# main.net
KiCad netlist of a schematic drawn in EAGLE
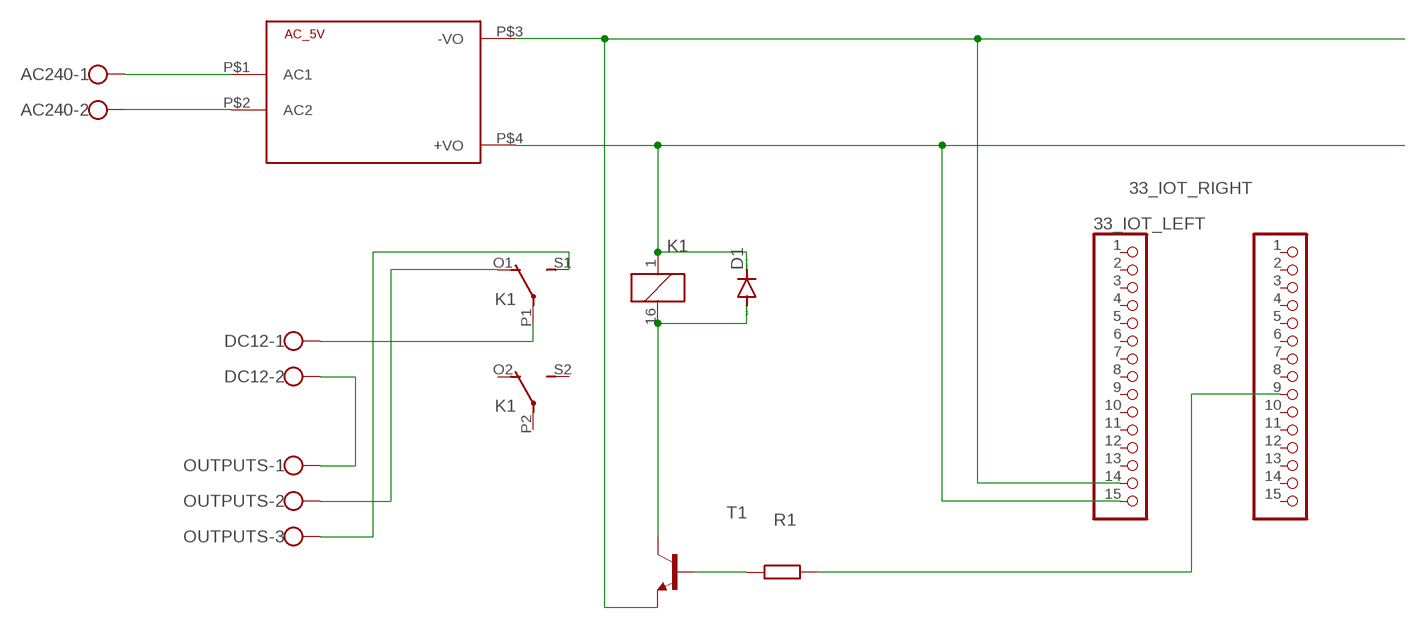
[diagram p0: schematic, sheet 1]

(export (version "E")
  (design (tool "Eeschema 10.0.6"))
  (components
    (comp (ref "33_IOT_LEFT")
      (value "PINHD-1X15")
      (footprint "eagle-import:1X15")
      (libsource (lib "eagle-import") (part "PINHD-1X15"))
    )
    (comp (ref "33_IOT_RIGHT")
      (value "PINHD-1X15")
      (footprint "eagle-import:1X15")
      (libsource (lib "eagle-import") (part "PINHD-1X15"))
    )
    (comp (ref "AC240")
      (value "W237-102")
      (footprint "eagle-import:W237-102")
      (fields (field (name "MPN") "237-102"))
      (libsource (lib "eagle-import") (part "W237-102"))
    )
    (comp (ref "AC_5V")
      (value "HLK-PM013W")
      (footprint "eagle-import:HLK-PM01")
      (libsource (lib "eagle-import") (part "HLK-PM013W"))
    )
    (comp (ref "D1")
      (value "1N5060GP")
      (footprint "eagle-import:DO15-12")
      (libsource (lib "eagle-import") (part "1N5060GP"))
    )
    (comp (ref "DC12")
      (value "W237-102")
      (footprint "eagle-import:W237-102")
      (fields (field (name "MPN") "237-102"))
      (libsource (lib "eagle-import") (part "W237-102"))
    )
    (comp (ref "K1")
      (value "351")
      (footprint "eagle-import:351")
      (libsource (lib "eagle-import") (part "351"))
    )
    (comp (ref "OUTPUTS")
      (value "W237-103")
      (footprint "eagle-import:W237-103")
      (fields (field (name "MPN") "237-103"))
      (libsource (lib "eagle-import") (part "W237-103"))
    )
    (comp (ref "R1")
      (value "R-EU_0207/10")
      (footprint "eagle-import:0207_10")
      (libsource (lib "eagle-import") (part "R-EU_0207/10"))
    )
    (comp (ref "T1")
      (value "2N2222")
      (footprint "eagle-import:TO18")
      (libsource (lib "eagle-import") (part "2N2222"))
    )
  )
  (nets
    (net (code "1") (name "Net-(33_IOT_RIGHT-Pad9)") (class "Default")
      (node (ref "33_IOT_RIGHT") (pin "9") (pinfunction "9_9") (pintype "passive"))
      (node (ref "R1") (pin "2") (pinfunction "2_2") (pintype "passive"))
    )
    (net (code "2") (name "Net-(AC240A-KL)") (class "Default")
      (node (ref "AC240") (pin "1") (pinfunction "KL_1") (pintype "passive"))
      (node (ref "AC_5V") (pin "P$1") (pinfunction "AC1_P$1") (pintype "bidirectional"))
    )
    (net (code "3") (name "Net-(AC240B-KL)") (class "Default")
      (node (ref "AC240") (pin "2") (pinfunction "KL_2") (pintype "passive"))
      (node (ref "AC_5V") (pin "P$2") (pinfunction "AC2_P$2") (pintype "bidirectional"))
    )
    (net (code "4") (name "Net-(AC_5V-+VO)") (class "Default")
      (node (ref "33_IOT_LEFT") (pin "15") (pinfunction "15_15") (pintype "passive"))
      (node (ref "AC_5V") (pin "P$4") (pinfunction "+VO_P$4") (pintype "bidirectional"))
      (node (ref "D1") (pin "C") (pinfunction "C_C") (pintype "passive"))
      (node (ref "K1") (pin "1") (pinfunction "1_1") (pintype "passive"))
    )
    (net (code "5") (name "Net-(AC_5V--VO)") (class "Default")
      (node (ref "33_IOT_LEFT") (pin "14") (pinfunction "14_14") (pintype "passive"))
      (node (ref "AC_5V") (pin "P$3") (pinfunction "-VO_P$3") (pintype "bidirectional"))
      (node (ref "T1") (pin "1") (pinfunction "E_1") (pintype "passive"))
    )
    (net (code "6") (name "Net-(DC12A-KL)") (class "Default")
      (node (ref "DC12") (pin "1") (pinfunction "KL_1") (pintype "passive"))
      (node (ref "K1") (pin "P1") (pinfunction "P_P1") (pintype "passive"))
    )
    (net (code "7") (name "Net-(DC12B-KL)") (class "Default")
      (node (ref "DC12") (pin "2") (pinfunction "KL_2") (pintype "passive"))
      (node (ref "OUTPUTS") (pin "1") (pinfunction "KL_1") (pintype "passive"))
    )
    (net (code "8") (name "Net-(K1A-2)") (class "Default")
      (node (ref "D1") (pin "A") (pinfunction "A_A") (pintype "passive"))
      (node (ref "K1") (pin "16") (pinfunction "2_16") (pintype "passive"))
      (node (ref "T1") (pin "3") (pinfunction "C_3") (pintype "passive"))
    )
    (net (code "9") (name "Net-(K1B-O)") (class "Default")
      (node (ref "K1") (pin "O1") (pinfunction "O_O1") (pintype "passive"))
      (node (ref "OUTPUTS") (pin "2") (pinfunction "KL_2") (pintype "passive"))
    )
    (net (code "10") (name "Net-(K1B-S)") (class "Default")
      (node (ref "K1") (pin "S1") (pinfunction "S_S1") (pintype "passive"))
      (node (ref "OUTPUTS") (pin "3") (pinfunction "KL_3") (pintype "passive"))
    )
    (net (code "11") (name "Net-(T1-B)") (class "Default")
      (node (ref "R1") (pin "1") (pinfunction "1_1") (pintype "passive"))
      (node (ref "T1") (pin "2") (pinfunction "B_2") (pintype "passive"))
    )
    (net (code "12") (name "unconnected-(33_IOT_LEFT-Pad1)") (class "Default")
      (node (ref "33_IOT_LEFT") (pin "1") (pinfunction "1_1") (pintype "passive"))
    )
    (net (code "13") (name "unconnected-(33_IOT_LEFT-Pad2)") (class "Default")
      (node (ref "33_IOT_LEFT") (pin "2") (pinfunction "2_2") (pintype "passive"))
    )
    (net (code "14") (name "unconnected-(33_IOT_LEFT-Pad3)") (class "Default")
      (node (ref "33_IOT_LEFT") (pin "3") (pinfunction "3_3") (pintype "passive"))
    )
    (net (code "15") (name "unconnected-(33_IOT_LEFT-Pad4)") (class "Default")
      (node (ref "33_IOT_LEFT") (pin "4") (pinfunction "4_4") (pintype "passive"))
    )
    (net (code "16") (name "unconnected-(33_IOT_LEFT-Pad5)") (class "Default")
      (node (ref "33_IOT_LEFT") (pin "5") (pinfunction "5_5") (pintype "passive"))
    )
    (net (code "17") (name "unconnected-(33_IOT_LEFT-Pad6)") (class "Default")
      (node (ref "33_IOT_LEFT") (pin "6") (pinfunction "6_6") (pintype "passive"))
    )
    (net (code "18") (name "unconnected-(33_IOT_LEFT-Pad7)") (class "Default")
      (node (ref "33_IOT_LEFT") (pin "7") (pinfunction "7_7") (pintype "passive"))
    )
    (net (code "19") (name "unconnected-(33_IOT_LEFT-Pad8)") (class "Default")
      (node (ref "33_IOT_LEFT") (pin "8") (pinfunction "8_8") (pintype "passive"))
    )
    (net (code "20") (name "unconnected-(33_IOT_LEFT-Pad9)") (class "Default")
      (node (ref "33_IOT_LEFT") (pin "9") (pinfunction "9_9") (pintype "passive"))
    )
    (net (code "21") (name "unconnected-(33_IOT_LEFT-Pad10)") (class "Default")
      (node (ref "33_IOT_LEFT") (pin "10") (pinfunction "10_10") (pintype "passive"))
    )
    (net (code "22") (name "unconnected-(33_IOT_LEFT-Pad11)") (class "Default")
      (node (ref "33_IOT_LEFT") (pin "11") (pinfunction "11_11") (pintype "passive"))
    )
    (net (code "23") (name "unconnected-(33_IOT_LEFT-Pad12)") (class "Default")
      (node (ref "33_IOT_LEFT") (pin "12") (pinfunction "12_12") (pintype "passive"))
    )
    (net (code "24") (name "unconnected-(33_IOT_LEFT-Pad13)") (class "Default")
      (node (ref "33_IOT_LEFT") (pin "13") (pinfunction "13_13") (pintype "passive"))
    )
    (net (code "25") (name "unconnected-(33_IOT_RIGHT-Pad1)") (class "Default")
      (node (ref "33_IOT_RIGHT") (pin "1") (pinfunction "1_1") (pintype "passive"))
    )
    (net (code "26") (name "unconnected-(33_IOT_RIGHT-Pad2)") (class "Default")
      (node (ref "33_IOT_RIGHT") (pin "2") (pinfunction "2_2") (pintype "passive"))
    )
    (net (code "27") (name "unconnected-(33_IOT_RIGHT-Pad3)") (class "Default")
      (node (ref "33_IOT_RIGHT") (pin "3") (pinfunction "3_3") (pintype "passive"))
    )
    (net (code "28") (name "unconnected-(33_IOT_RIGHT-Pad4)") (class "Default")
      (node (ref "33_IOT_RIGHT") (pin "4") (pinfunction "4_4") (pintype "passive"))
    )
    (net (code "29") (name "unconnected-(33_IOT_RIGHT-Pad5)") (class "Default")
      (node (ref "33_IOT_RIGHT") (pin "5") (pinfunction "5_5") (pintype "passive"))
    )
    (net (code "30") (name "unconnected-(33_IOT_RIGHT-Pad6)") (class "Default")
      (node (ref "33_IOT_RIGHT") (pin "6") (pinfunction "6_6") (pintype "passive"))
    )
    (net (code "31") (name "unconnected-(33_IOT_RIGHT-Pad7)") (class "Default")
      (node (ref "33_IOT_RIGHT") (pin "7") (pinfunction "7_7") (pintype "passive"))
    )
    (net (code "32") (name "unconnected-(33_IOT_RIGHT-Pad8)") (class "Default")
      (node (ref "33_IOT_RIGHT") (pin "8") (pinfunction "8_8") (pintype "passive"))
    )
    (net (code "33") (name "unconnected-(33_IOT_RIGHT-Pad10)") (class "Default")
      (node (ref "33_IOT_RIGHT") (pin "10") (pinfunction "10_10") (pintype "passive"))
    )
    (net (code "34") (name "unconnected-(33_IOT_RIGHT-Pad11)") (class "Default")
      (node (ref "33_IOT_RIGHT") (pin "11") (pinfunction "11_11") (pintype "passive"))
    )
    (net (code "35") (name "unconnected-(33_IOT_RIGHT-Pad12)") (class "Default")
      (node (ref "33_IOT_RIGHT") (pin "12") (pinfunction "12_12") (pintype "passive"))
    )
    (net (code "36") (name "unconnected-(33_IOT_RIGHT-Pad13)") (class "Default")
      (node (ref "33_IOT_RIGHT") (pin "13") (pinfunction "13_13") (pintype "passive"))
    )
    (net (code "37") (name "unconnected-(33_IOT_RIGHT-Pad14)") (class "Default")
      (node (ref "33_IOT_RIGHT") (pin "14") (pinfunction "14_14") (pintype "passive"))
    )
    (net (code "38") (name "unconnected-(33_IOT_RIGHT-Pad15)") (class "Default")
      (node (ref "33_IOT_RIGHT") (pin "15") (pinfunction "15_15") (pintype "passive"))
    )
    (net (code "39") (name "unconnected-(K1C-O-PadO2)") (class "Default")
      (node (ref "K1") (pin "O2") (pinfunction "O_O2") (pintype "passive"))
    )
    (net (code "40") (name "unconnected-(K1C-P-PadP2)") (class "Default")
      (node (ref "K1") (pin "P2") (pinfunction "P_P2") (pintype "passive"))
    )
    (net (code "41") (name "unconnected-(K1C-S-PadS2)") (class "Default")
      (node (ref "K1") (pin "S2") (pinfunction "S_S2") (pintype "passive"))
    )
  )
)
